# MCUs.net
KiCad netlist of a schematic drawn in Altium Designer
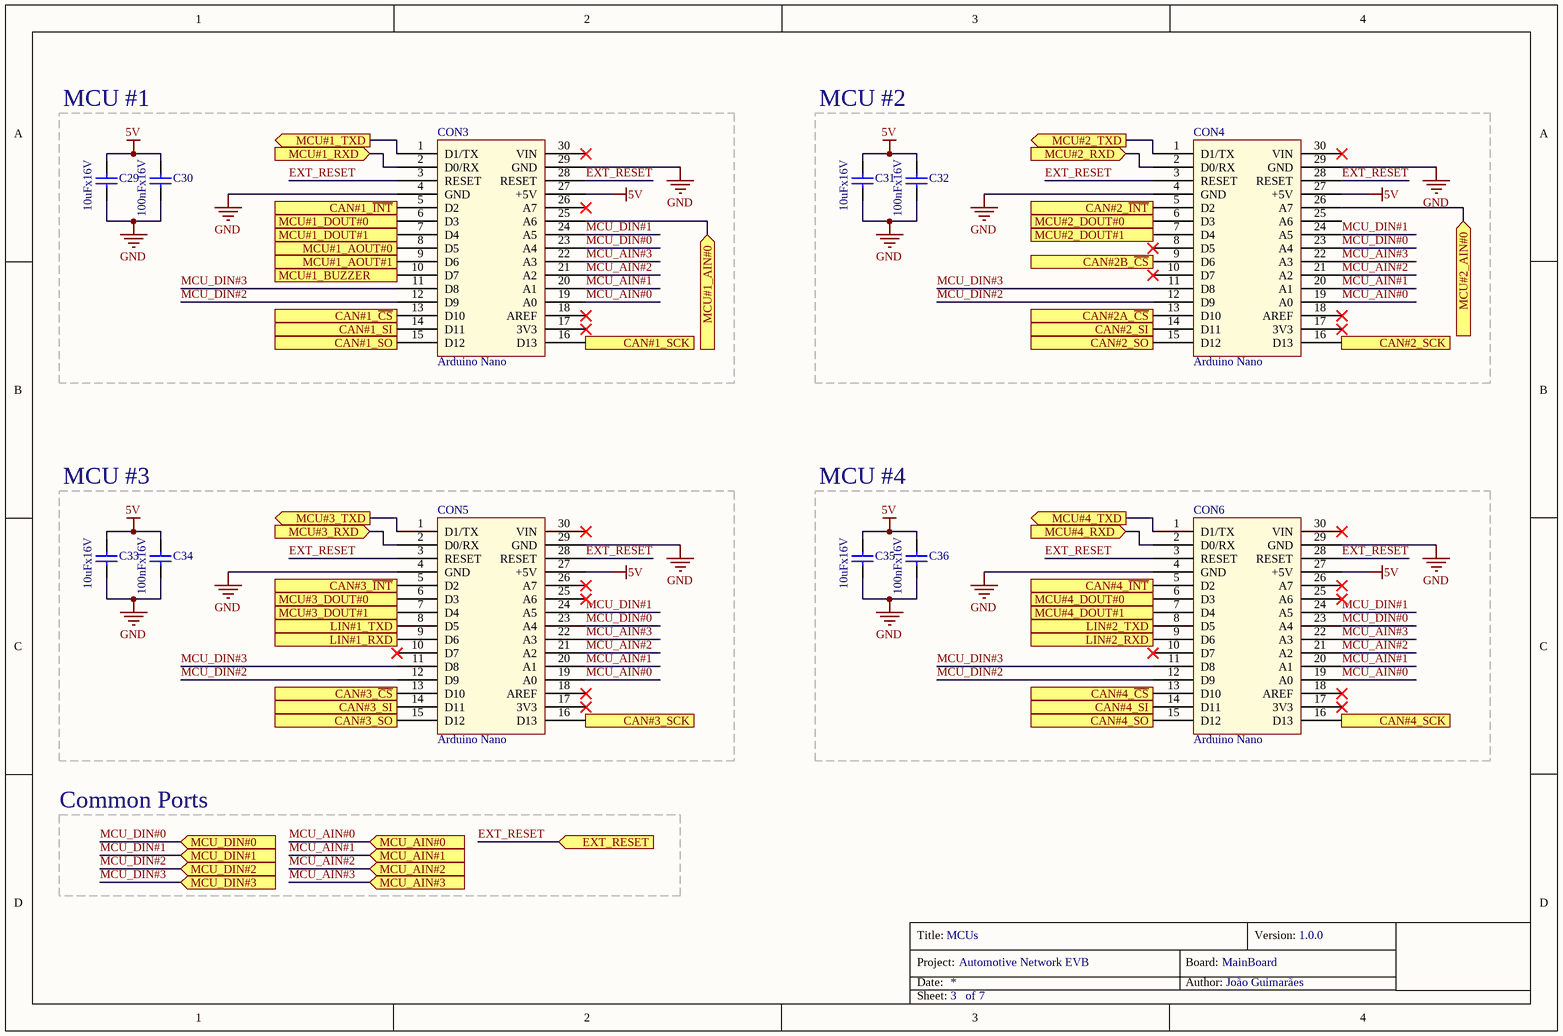
[diagram p0: MCUs.SchDoc]

(export (version "E")
  (design (tool "Eeschema 10.0.6"))
  (components
    (comp (ref "C29")
      (value "10uFx16V")
      (footprint "DISC-0805")
      (description "Capacitor")
      (libsource (lib "IntLib") (part "Cap"))
    )
    (comp (ref "C30")
      (value "100nFx16V")
      (footprint "DISC-0603")
      (description "Capacitor")
      (libsource (lib "IntLib") (part "Cap"))
    )
    (comp (ref "C31")
      (value "10uFx16V")
      (footprint "DISC-0805")
      (description "Capacitor")
      (libsource (lib "IntLib") (part "Cap"))
    )
    (comp (ref "C32")
      (value "100nFx16V")
      (footprint "DISC-0603")
      (description "Capacitor")
      (libsource (lib "IntLib") (part "Cap"))
    )
    (comp (ref "C33")
      (value "10uFx16V")
      (footprint "DISC-0805")
      (description "Capacitor")
      (libsource (lib "IntLib") (part "Cap"))
    )
    (comp (ref "C34")
      (value "100nFx16V")
      (footprint "DISC-0603")
      (description "Capacitor")
      (libsource (lib "IntLib") (part "Cap"))
    )
    (comp (ref "C35")
      (value "10uFx16V")
      (footprint "DISC-0805")
      (description "Capacitor")
      (libsource (lib "IntLib") (part "Cap"))
    )
    (comp (ref "C36")
      (value "100nFx16V")
      (footprint "DISC-0603")
      (description "Capacitor")
      (libsource (lib "IntLib") (part "Cap"))
    )
    (comp (ref "CON3")
      (value "Arduino Nano")
      (footprint "MOD-ARDUINO-NANO")
      (libsource (lib "IntLib") (part "Arduino Nano"))
    )
    (comp (ref "CON4")
      (value "Arduino Nano")
      (footprint "MOD-ARDUINO-NANO")
      (libsource (lib "IntLib") (part "Arduino Nano"))
    )
    (comp (ref "CON5")
      (value "Arduino Nano")
      (footprint "MOD-ARDUINO-NANO")
      (libsource (lib "IntLib") (part "Arduino Nano"))
    )
    (comp (ref "CON6")
      (value "Arduino Nano")
      (footprint "MOD-ARDUINO-NANO")
      (libsource (lib "IntLib") (part "Arduino Nano"))
    )
  )
  (nets
    (net (code "1") (name "/CAN#1_SCK") (class "Default")
      (node (ref "CON3") (pin "16") (pinfunction "D13_16") (pintype "passive"))
    )
    (net (code "2") (name "/CAN#1_SI") (class "Default")
      (node (ref "CON3") (pin "14") (pinfunction "D11_14") (pintype "passive"))
    )
    (net (code "3") (name "/CAN#1_SO") (class "Default")
      (node (ref "CON3") (pin "15") (pinfunction "D12_15") (pintype "passive"))
    )
    (net (code "4") (name "/CAN#1_~{CS}") (class "Default")
      (node (ref "CON3") (pin "13") (pinfunction "D10_13") (pintype "passive"))
    )
    (net (code "5") (name "/CAN#1_~{INT}") (class "Default")
      (node (ref "CON3") (pin "5") (pinfunction "D2_5") (pintype "passive"))
    )
    (net (code "6") (name "/CAN#2A_~{CS}") (class "Default")
      (node (ref "CON4") (pin "13") (pinfunction "D10_13") (pintype "passive"))
    )
    (net (code "7") (name "/CAN#2B_~{CS}") (class "Default")
      (node (ref "CON4") (pin "9") (pinfunction "D6_9") (pintype "passive"))
    )
    (net (code "8") (name "/CAN#2_SCK") (class "Default")
      (node (ref "CON4") (pin "16") (pinfunction "D13_16") (pintype "passive"))
    )
    (net (code "9") (name "/CAN#2_SI") (class "Default")
      (node (ref "CON4") (pin "14") (pinfunction "D11_14") (pintype "passive"))
    )
    (net (code "10") (name "/CAN#2_SO") (class "Default")
      (node (ref "CON4") (pin "15") (pinfunction "D12_15") (pintype "passive"))
    )
    (net (code "11") (name "/CAN#2_~{INT}") (class "Default")
      (node (ref "CON4") (pin "5") (pinfunction "D2_5") (pintype "passive"))
    )
    (net (code "12") (name "/CAN#3_SCK") (class "Default")
      (node (ref "CON5") (pin "16") (pinfunction "D13_16") (pintype "passive"))
    )
    (net (code "13") (name "/CAN#3_SI") (class "Default")
      (node (ref "CON5") (pin "14") (pinfunction "D11_14") (pintype "passive"))
    )
    (net (code "14") (name "/CAN#3_SO") (class "Default")
      (node (ref "CON5") (pin "15") (pinfunction "D12_15") (pintype "passive"))
    )
    (net (code "15") (name "/CAN#3_~{CS}") (class "Default")
      (node (ref "CON5") (pin "13") (pinfunction "D10_13") (pintype "passive"))
    )
    (net (code "16") (name "/CAN#3_~{INT}") (class "Default")
      (node (ref "CON5") (pin "5") (pinfunction "D2_5") (pintype "passive"))
    )
    (net (code "17") (name "/CAN#4_SCK") (class "Default")
      (node (ref "CON6") (pin "16") (pinfunction "D13_16") (pintype "passive"))
    )
    (net (code "18") (name "/CAN#4_SI") (class "Default")
      (node (ref "CON6") (pin "14") (pinfunction "D11_14") (pintype "passive"))
    )
    (net (code "19") (name "/CAN#4_SO") (class "Default")
      (node (ref "CON6") (pin "15") (pinfunction "D12_15") (pintype "passive"))
    )
    (net (code "20") (name "/CAN#4_~{CS}") (class "Default")
      (node (ref "CON6") (pin "13") (pinfunction "D10_13") (pintype "passive"))
    )
    (net (code "21") (name "/CAN#4_~{INT}") (class "Default")
      (node (ref "CON6") (pin "5") (pinfunction "D2_5") (pintype "passive"))
    )
    (net (code "22") (name "/EXT_RESET") (class "Default")
      (node (ref "CON3") (pin "28") (pinfunction "RESET_28") (pintype "passive"))
      (node (ref "CON3") (pin "3") (pinfunction "RESET_3") (pintype "passive"))
      (node (ref "CON4") (pin "28") (pinfunction "RESET_28") (pintype "passive"))
      (node (ref "CON4") (pin "3") (pinfunction "RESET_3") (pintype "passive"))
      (node (ref "CON5") (pin "28") (pinfunction "RESET_28") (pintype "passive"))
      (node (ref "CON5") (pin "3") (pinfunction "RESET_3") (pintype "passive"))
      (node (ref "CON6") (pin "28") (pinfunction "RESET_28") (pintype "passive"))
      (node (ref "CON6") (pin "3") (pinfunction "RESET_3") (pintype "passive"))
    )
    (net (code "23") (name "/LIN#1_RXD") (class "Default")
      (node (ref "CON5") (pin "9") (pinfunction "D6_9") (pintype "passive"))
    )
    (net (code "24") (name "/LIN#1_TXD") (class "Default")
      (node (ref "CON5") (pin "8") (pinfunction "D5_8") (pintype "passive"))
    )
    (net (code "25") (name "/LIN#2_RXD") (class "Default")
      (node (ref "CON6") (pin "9") (pinfunction "D6_9") (pintype "passive"))
    )
    (net (code "26") (name "/LIN#2_TXD") (class "Default")
      (node (ref "CON6") (pin "8") (pinfunction "D5_8") (pintype "passive"))
    )
    (net (code "27") (name "/MCU#1_AIN#0") (class "Default")
      (node (ref "CON3") (pin "25") (pinfunction "A6_25") (pintype "passive"))
    )
    (net (code "28") (name "/MCU#1_AOUT#0") (class "Default")
      (node (ref "CON3") (pin "8") (pinfunction "D5_8") (pintype "passive"))
    )
    (net (code "29") (name "/MCU#1_AOUT#1") (class "Default")
      (node (ref "CON3") (pin "9") (pinfunction "D6_9") (pintype "passive"))
    )
    (net (code "30") (name "/MCU#1_BUZZER") (class "Default")
      (node (ref "CON3") (pin "10") (pinfunction "D7_10") (pintype "passive"))
    )
    (net (code "31") (name "/MCU#1_DOUT#0") (class "Default")
      (node (ref "CON3") (pin "6") (pinfunction "D3_6") (pintype "passive"))
    )
    (net (code "32") (name "/MCU#1_DOUT#1") (class "Default")
      (node (ref "CON3") (pin "7") (pinfunction "D4_7") (pintype "passive"))
    )
    (net (code "33") (name "/MCU#1_RXD") (class "Default")
      (node (ref "CON3") (pin "2") (pinfunction "D0/RX_2") (pintype "passive"))
    )
    (net (code "34") (name "/MCU#1_TXD") (class "Default")
      (node (ref "CON3") (pin "1") (pinfunction "D1/TX_1") (pintype "passive"))
    )
    (net (code "35") (name "/MCU#2_AIN#0") (class "Default")
      (node (ref "CON4") (pin "26") (pinfunction "A7_26") (pintype "passive"))
    )
    (net (code "36") (name "/MCU#2_DOUT#0") (class "Default")
      (node (ref "CON4") (pin "6") (pinfunction "D3_6") (pintype "passive"))
    )
    (net (code "37") (name "/MCU#2_DOUT#1") (class "Default")
      (node (ref "CON4") (pin "7") (pinfunction "D4_7") (pintype "passive"))
    )
    (net (code "38") (name "/MCU#2_RXD") (class "Default")
      (node (ref "CON4") (pin "2") (pinfunction "D0/RX_2") (pintype "passive"))
    )
    (net (code "39") (name "/MCU#2_TXD") (class "Default")
      (node (ref "CON4") (pin "1") (pinfunction "D1/TX_1") (pintype "passive"))
    )
    (net (code "40") (name "/MCU#3_DOUT#0") (class "Default")
      (node (ref "CON5") (pin "6") (pinfunction "D3_6") (pintype "passive"))
    )
    (net (code "41") (name "/MCU#3_DOUT#1") (class "Default")
      (node (ref "CON5") (pin "7") (pinfunction "D4_7") (pintype "passive"))
    )
    (net (code "42") (name "/MCU#3_RXD") (class "Default")
      (node (ref "CON5") (pin "2") (pinfunction "D0/RX_2") (pintype "passive"))
    )
    (net (code "43") (name "/MCU#3_TXD") (class "Default")
      (node (ref "CON5") (pin "1") (pinfunction "D1/TX_1") (pintype "passive"))
    )
    (net (code "44") (name "/MCU#4_DOUT#0") (class "Default")
      (node (ref "CON6") (pin "6") (pinfunction "D3_6") (pintype "passive"))
    )
    (net (code "45") (name "/MCU#4_DOUT#1") (class "Default")
      (node (ref "CON6") (pin "7") (pinfunction "D4_7") (pintype "passive"))
    )
    (net (code "46") (name "/MCU#4_RXD") (class "Default")
      (node (ref "CON6") (pin "2") (pinfunction "D0/RX_2") (pintype "passive"))
    )
    (net (code "47") (name "/MCU#4_TXD") (class "Default")
      (node (ref "CON6") (pin "1") (pinfunction "D1/TX_1") (pintype "passive"))
    )
    (net (code "48") (name "/MCU_AIN#0") (class "Default")
      (node (ref "CON3") (pin "19") (pinfunction "A0_19") (pintype "passive"))
      (node (ref "CON4") (pin "19") (pinfunction "A0_19") (pintype "passive"))
      (node (ref "CON5") (pin "19") (pinfunction "A0_19") (pintype "passive"))
      (node (ref "CON6") (pin "19") (pinfunction "A0_19") (pintype "passive"))
    )
    (net (code "49") (name "/MCU_AIN#1") (class "Default")
      (node (ref "CON3") (pin "20") (pinfunction "A1_20") (pintype "passive"))
      (node (ref "CON4") (pin "20") (pinfunction "A1_20") (pintype "passive"))
      (node (ref "CON5") (pin "20") (pinfunction "A1_20") (pintype "passive"))
      (node (ref "CON6") (pin "20") (pinfunction "A1_20") (pintype "passive"))
    )
    (net (code "50") (name "/MCU_AIN#2") (class "Default")
      (node (ref "CON3") (pin "21") (pinfunction "A2_21") (pintype "passive"))
      (node (ref "CON4") (pin "21") (pinfunction "A2_21") (pintype "passive"))
      (node (ref "CON5") (pin "21") (pinfunction "A2_21") (pintype "passive"))
      (node (ref "CON6") (pin "21") (pinfunction "A2_21") (pintype "passive"))
    )
    (net (code "51") (name "/MCU_AIN#3") (class "Default")
      (node (ref "CON3") (pin "22") (pinfunction "A3_22") (pintype "passive"))
      (node (ref "CON4") (pin "22") (pinfunction "A3_22") (pintype "passive"))
      (node (ref "CON5") (pin "22") (pinfunction "A3_22") (pintype "passive"))
      (node (ref "CON6") (pin "22") (pinfunction "A3_22") (pintype "passive"))
    )
    (net (code "52") (name "/MCU_DIN#0") (class "Default")
      (node (ref "CON3") (pin "23") (pinfunction "A4_23") (pintype "passive"))
      (node (ref "CON4") (pin "23") (pinfunction "A4_23") (pintype "passive"))
      (node (ref "CON5") (pin "23") (pinfunction "A4_23") (pintype "passive"))
      (node (ref "CON6") (pin "23") (pinfunction "A4_23") (pintype "passive"))
    )
    (net (code "53") (name "/MCU_DIN#1") (class "Default")
      (node (ref "CON3") (pin "24") (pinfunction "A5_24") (pintype "passive"))
      (node (ref "CON4") (pin "24") (pinfunction "A5_24") (pintype "passive"))
      (node (ref "CON5") (pin "24") (pinfunction "A5_24") (pintype "passive"))
      (node (ref "CON6") (pin "24") (pinfunction "A5_24") (pintype "passive"))
    )
    (net (code "54") (name "/MCU_DIN#2") (class "Default")
      (node (ref "CON3") (pin "12") (pinfunction "D9_12") (pintype "passive"))
      (node (ref "CON4") (pin "12") (pinfunction "D9_12") (pintype "passive"))
      (node (ref "CON5") (pin "12") (pinfunction "D9_12") (pintype "passive"))
      (node (ref "CON6") (pin "12") (pinfunction "D9_12") (pintype "passive"))
    )
    (net (code "55") (name "/MCU_DIN#3") (class "Default")
      (node (ref "CON3") (pin "11") (pinfunction "D8_11") (pintype "passive"))
      (node (ref "CON4") (pin "11") (pinfunction "D8_11") (pintype "passive"))
      (node (ref "CON5") (pin "11") (pinfunction "D8_11") (pintype "passive"))
      (node (ref "CON6") (pin "11") (pinfunction "D8_11") (pintype "passive"))
    )
    (net (code "56") (name "5V") (class "Default")
      (node (ref "C29") (pin "1") (pinfunction "1_1") (pintype "passive"))
      (node (ref "C30") (pin "1") (pinfunction "1_1") (pintype "passive"))
      (node (ref "C31") (pin "1") (pinfunction "1_1") (pintype "passive"))
      (node (ref "C32") (pin "1") (pinfunction "1_1") (pintype "passive"))
      (node (ref "C33") (pin "1") (pinfunction "1_1") (pintype "passive"))
      (node (ref "C34") (pin "1") (pinfunction "1_1") (pintype "passive"))
      (node (ref "C35") (pin "1") (pinfunction "1_1") (pintype "passive"))
      (node (ref "C36") (pin "1") (pinfunction "1_1") (pintype "passive"))
      (node (ref "CON3") (pin "27") (pinfunction "+5V_27") (pintype "passive"))
      (node (ref "CON4") (pin "27") (pinfunction "+5V_27") (pintype "passive"))
      (node (ref "CON5") (pin "27") (pinfunction "+5V_27") (pintype "passive"))
      (node (ref "CON6") (pin "27") (pinfunction "+5V_27") (pintype "passive"))
    )
    (net (code "57") (name "GND") (class "Default")
      (node (ref "C29") (pin "2") (pinfunction "2_2") (pintype "passive"))
      (node (ref "C30") (pin "2") (pinfunction "2_2") (pintype "passive"))
      (node (ref "C31") (pin "2") (pinfunction "2_2") (pintype "passive"))
      (node (ref "C32") (pin "2") (pinfunction "2_2") (pintype "passive"))
      (node (ref "C33") (pin "2") (pinfunction "2_2") (pintype "passive"))
      (node (ref "C34") (pin "2") (pinfunction "2_2") (pintype "passive"))
      (node (ref "C35") (pin "2") (pinfunction "2_2") (pintype "passive"))
      (node (ref "C36") (pin "2") (pinfunction "2_2") (pintype "passive"))
      (node (ref "CON3") (pin "29") (pinfunction "GND_29") (pintype "passive"))
      (node (ref "CON3") (pin "4") (pinfunction "GND_4") (pintype "passive"))
      (node (ref "CON4") (pin "29") (pinfunction "GND_29") (pintype "passive"))
      (node (ref "CON4") (pin "4") (pinfunction "GND_4") (pintype "passive"))
      (node (ref "CON5") (pin "29") (pinfunction "GND_29") (pintype "passive"))
      (node (ref "CON5") (pin "4") (pinfunction "GND_4") (pintype "passive"))
      (node (ref "CON6") (pin "29") (pinfunction "GND_29") (pintype "passive"))
      (node (ref "CON6") (pin "4") (pinfunction "GND_4") (pintype "passive"))
    )
    (net (code "58") (name "unconnected-(CON3-3V3-Pad17)") (class "Default")
      (node (ref "CON3") (pin "17") (pinfunction "3V3_17") (pintype "passive+no_connect"))
    )
    (net (code "59") (name "unconnected-(CON3-A7-Pad26)") (class "Default")
      (node (ref "CON3") (pin "26") (pinfunction "A7_26") (pintype "passive+no_connect"))
    )
    (net (code "60") (name "unconnected-(CON3-AREF-Pad18)") (class "Default")
      (node (ref "CON3") (pin "18") (pinfunction "AREF_18") (pintype "passive+no_connect"))
    )
    (net (code "61") (name "unconnected-(CON3-VIN-Pad30)") (class "Default")
      (node (ref "CON3") (pin "30") (pinfunction "VIN_30") (pintype "passive+no_connect"))
    )
    (net (code "62") (name "unconnected-(CON4-3V3-Pad17)") (class "Default")
      (node (ref "CON4") (pin "17") (pinfunction "3V3_17") (pintype "passive+no_connect"))
    )
    (net (code "63") (name "unconnected-(CON4-A6-Pad25)") (class "Default")
      (node (ref "CON4") (pin "25") (pinfunction "A6_25") (pintype "passive"))
    )
    (net (code "64") (name "unconnected-(CON4-AREF-Pad18)") (class "Default")
      (node (ref "CON4") (pin "18") (pinfunction "AREF_18") (pintype "passive+no_connect"))
    )
    (net (code "65") (name "unconnected-(CON4-D5-Pad8)") (class "Default")
      (node (ref "CON4") (pin "8") (pinfunction "D5_8") (pintype "passive+no_connect"))
    )
    (net (code "66") (name "unconnected-(CON4-D7-Pad10)") (class "Default")
      (node (ref "CON4") (pin "10") (pinfunction "D7_10") (pintype "passive+no_connect"))
    )
    (net (code "67") (name "unconnected-(CON4-VIN-Pad30)") (class "Default")
      (node (ref "CON4") (pin "30") (pinfunction "VIN_30") (pintype "passive+no_connect"))
    )
    (net (code "68") (name "unconnected-(CON5-3V3-Pad17)") (class "Default")
      (node (ref "CON5") (pin "17") (pinfunction "3V3_17") (pintype "passive+no_connect"))
    )
    (net (code "69") (name "unconnected-(CON5-A6-Pad25)") (class "Default")
      (node (ref "CON5") (pin "25") (pinfunction "A6_25") (pintype "passive+no_connect"))
    )
    (net (code "70") (name "unconnected-(CON5-A7-Pad26)") (class "Default")
      (node (ref "CON5") (pin "26") (pinfunction "A7_26") (pintype "passive+no_connect"))
    )
    (net (code "71") (name "unconnected-(CON5-AREF-Pad18)") (class "Default")
      (node (ref "CON5") (pin "18") (pinfunction "AREF_18") (pintype "passive+no_connect"))
    )
    (net (code "72") (name "unconnected-(CON5-D7-Pad10)") (class "Default")
      (node (ref "CON5") (pin "10") (pinfunction "D7_10") (pintype "passive+no_connect"))
    )
    (net (code "73") (name "unconnected-(CON5-VIN-Pad30)") (class "Default")
      (node (ref "CON5") (pin "30") (pinfunction "VIN_30") (pintype "passive+no_connect"))
    )
    (net (code "74") (name "unconnected-(CON6-3V3-Pad17)") (class "Default")
      (node (ref "CON6") (pin "17") (pinfunction "3V3_17") (pintype "passive+no_connect"))
    )
    (net (code "75") (name "unconnected-(CON6-A6-Pad25)") (class "Default")
      (node (ref "CON6") (pin "25") (pinfunction "A6_25") (pintype "passive+no_connect"))
    )
    (net (code "76") (name "unconnected-(CON6-A7-Pad26)") (class "Default")
      (node (ref "CON6") (pin "26") (pinfunction "A7_26") (pintype "passive+no_connect"))
    )
    (net (code "77") (name "unconnected-(CON6-AREF-Pad18)") (class "Default")
      (node (ref "CON6") (pin "18") (pinfunction "AREF_18") (pintype "passive+no_connect"))
    )
    (net (code "78") (name "unconnected-(CON6-D7-Pad10)") (class "Default")
      (node (ref "CON6") (pin "10") (pinfunction "D7_10") (pintype "passive+no_connect"))
    )
    (net (code "79") (name "unconnected-(CON6-VIN-Pad30)") (class "Default")
      (node (ref "CON6") (pin "30") (pinfunction "VIN_30") (pintype "passive+no_connect"))
    )
  )
)
